# hamp2.net
KiCad netlist of a schematic drawn in EAGLE
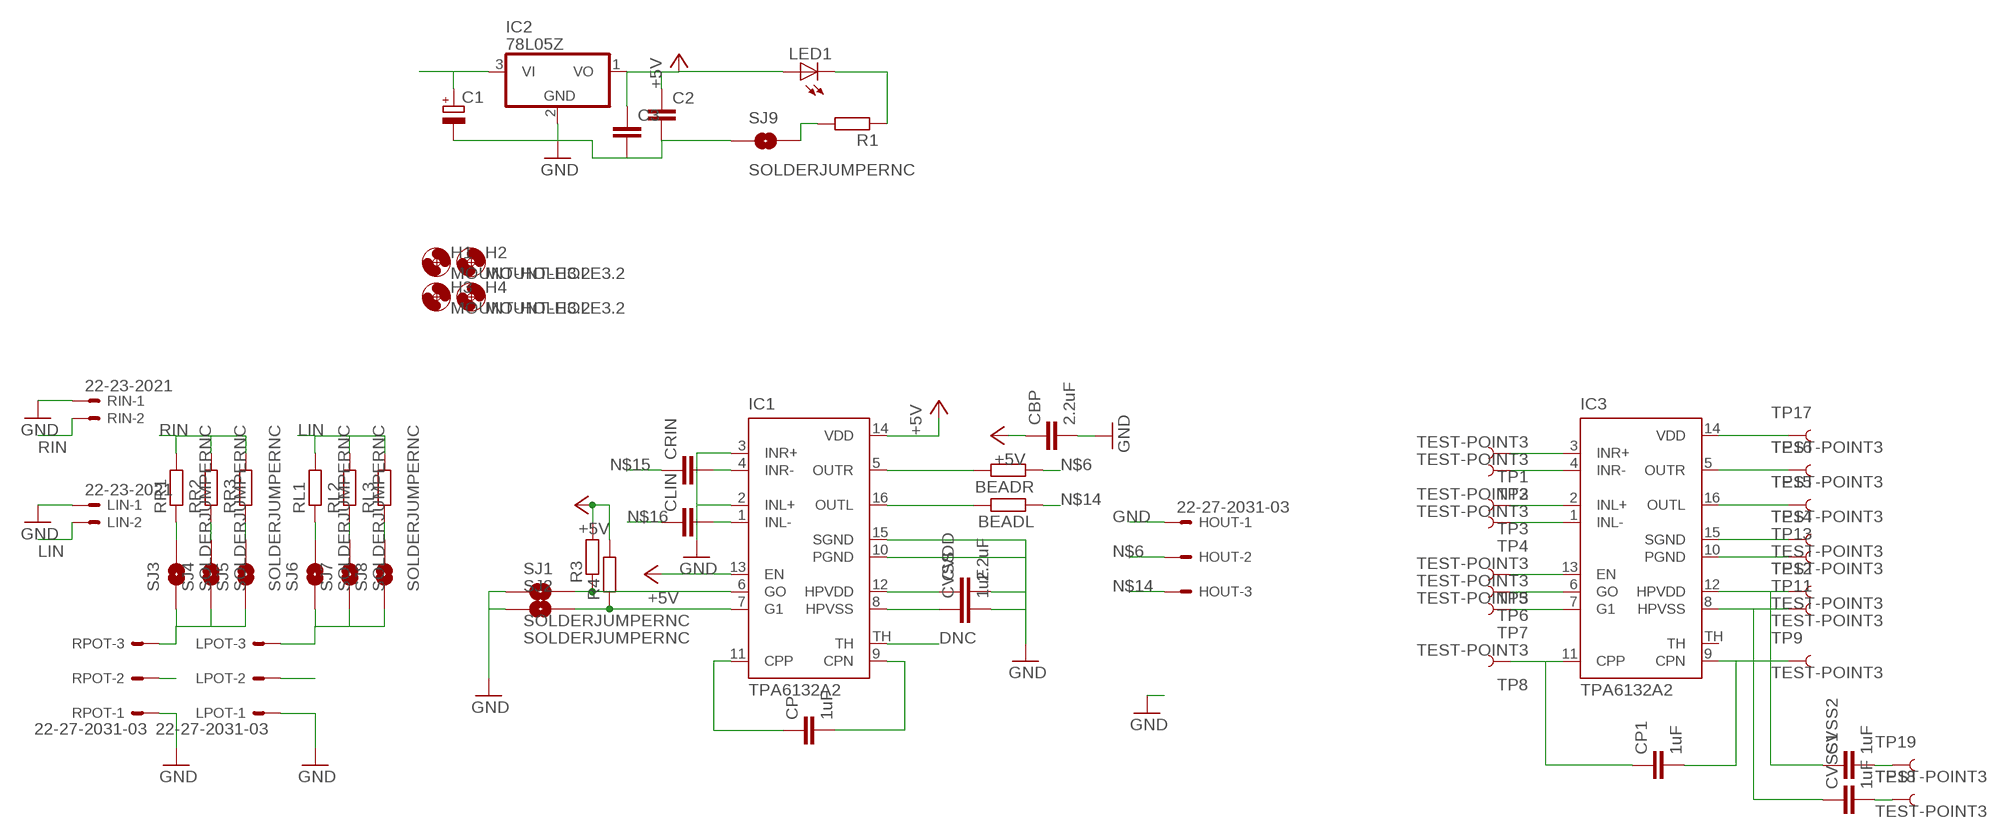
[diagram p0: schematic, sheet 1]

(export (version "E")
  (design (tool "Eeschema 10.0.6"))
  (components
    (comp (ref "BEADL")
      (value "R-EU_R0805")
      (footprint "eagle-import:R0805")
      (libsource (lib "eagle-import") (part "R-EU_R0805"))
    )
    (comp (ref "BEADR")
      (value "R-EU_R0805")
      (footprint "eagle-import:R0805")
      (libsource (lib "eagle-import") (part "R-EU_R0805"))
    )
    (comp (ref "C1")
      (value "CPOL-EUF")
      (footprint "eagle-import:PANASONIC_F")
      (libsource (lib "eagle-import") (part "CPOL-EUF"))
    )
    (comp (ref "C2")
      (value "C-EUC1210")
      (footprint "eagle-import:C1210")
      (libsource (lib "eagle-import") (part "resistor_C-EUC1210"))
    )
    (comp (ref "C3")
      (value "C-EUC0805")
      (footprint "eagle-import:C0805")
      (libsource (lib "eagle-import") (part "resistor_C-EUC0805"))
    )
    (comp (ref "CBP")
      (value "2.2uF")
      (footprint "eagle-import:C0805")
      (libsource (lib "eagle-import") (part "resistor_C-EUC0805"))
    )
    (comp (ref "CLIN")
      (value "C-EU050-055X075")
      (footprint "eagle-import:C050-055X075")
      (libsource (lib "eagle-import") (part "C-EU050-055X075"))
    )
    (comp (ref "CP")
      (value "1uF")
      (footprint "eagle-import:C0805")
      (libsource (lib "eagle-import") (part "resistor_C-EUC0805"))
    )
    (comp (ref "CP1")
      (value "1uF")
      (footprint "eagle-import:C0805")
      (libsource (lib "eagle-import") (part "resistor_C-EUC0805"))
    )
    (comp (ref "CRIN")
      (value "C-EU050-055X075")
      (footprint "eagle-import:C050-055X075")
      (libsource (lib "eagle-import") (part "C-EU050-055X075"))
    )
    (comp (ref "CVDD")
      (value "2.2uF")
      (footprint "eagle-import:C0805")
      (libsource (lib "eagle-import") (part "resistor_C-EUC0805"))
    )
    (comp (ref "CVSS")
      (value "1uF")
      (footprint "eagle-import:C0805")
      (libsource (lib "eagle-import") (part "resistor_C-EUC0805"))
    )
    (comp (ref "CVSS1")
      (value "1uF")
      (footprint "eagle-import:C0805")
      (libsource (lib "eagle-import") (part "resistor_C-EUC0805"))
    )
    (comp (ref "CVSS2")
      (value "1uF")
      (footprint "eagle-import:C0805")
      (libsource (lib "eagle-import") (part "resistor_C-EUC0805"))
    )
    (comp (ref "H1")
      (value "MOUNT-HOLE3.2")
      (footprint "eagle-import:3,2")
      (libsource (lib "eagle-import") (part "MOUNT-HOLE3.2"))
    )
    (comp (ref "H2")
      (value "MOUNT-HOLE3.2")
      (footprint "eagle-import:3,2")
      (libsource (lib "eagle-import") (part "MOUNT-HOLE3.2"))
    )
    (comp (ref "H3")
      (value "MOUNT-HOLE3.2")
      (footprint "eagle-import:3,2")
      (libsource (lib "eagle-import") (part "MOUNT-HOLE3.2"))
    )
    (comp (ref "H4")
      (value "MOUNT-HOLE3.2")
      (footprint "eagle-import:3,2")
      (libsource (lib "eagle-import") (part "MOUNT-HOLE3.2"))
    )
    (comp (ref "HOUT")
      (value "22-27-2031-03")
      (footprint "eagle-import:6410-03")
      (fields (field (name "OC_FARNELL") "unknown") (field (name "OC_NEWARK") "unknown"))
      (libsource (lib "eagle-import") (part "22-?-0327-2031"))
    )
    (comp (ref "IC1")
      (value "TPA6132A2")
      (footprint "eagle-import:QFN16")
      (fields (field (name "MPN") "TPA6132A2RTET"))
      (libsource (lib "eagle-import") (part "TPA6132A2"))
    )
    (comp (ref "IC2")
      (value "78L05Z")
      (footprint "eagle-import:TO92")
      (libsource (lib "eagle-import") (part "78ZL05"))
    )
    (comp (ref "IC3")
      (value "TPA6132A2")
      (footprint "eagle-import:QFN16")
      (fields
        (field (name "MPN") "TPA6132A2RTET")
        (field (name "MPN_1") "TPA6132A2RTET")
        (field (name "OC_FARNELL") "1697167")
        (field (name "OC_NEWARK") "46P3781")
      )
      (libsource (lib "eagle-import") (part "TPA6132A2"))
    )
    (comp (ref "LED1")
      (value "LEDCHIP-LED0805")
      (footprint "eagle-import:CHIP-LED0805")
      (libsource (lib "eagle-import") (part "LEDCHIP-LED0805"))
    )
    (comp (ref "LIN")
      (value "22-23-2021")
      (footprint "eagle-import:22-23-2021")
      (fields (field (name "MF") "MOLEX"))
      (libsource (lib "eagle-import") (part "22-23-2021"))
    )
    (comp (ref "LPOT")
      (value "22-27-2031-03")
      (footprint "eagle-import:6410-03")
      (fields (field (name "OC_FARNELL") "unknown") (field (name "OC_NEWARK") "unknown"))
      (libsource (lib "eagle-import") (part "22-?-0327-2031"))
    )
    (comp (ref "R1")
      (value "R-EU_R0805")
      (footprint "eagle-import:R0805")
      (libsource (lib "eagle-import") (part "R-EU_R0805"))
    )
    (comp (ref "R3")
      (value "R-EU_R0805")
      (footprint "eagle-import:R0805")
      (libsource (lib "eagle-import") (part "R-EU_R0805"))
    )
    (comp (ref "R4")
      (value "R-EU_R0805")
      (footprint "eagle-import:R0805")
      (libsource (lib "eagle-import") (part "R-EU_R0805"))
    )
    (comp (ref "RIN")
      (value "22-23-2021")
      (footprint "eagle-import:22-23-2021")
      (fields (field (name "MF") "MOLEX"))
      (libsource (lib "eagle-import") (part "22-23-2021"))
    )
    (comp (ref "RL1")
      (value "R-EU_R0805")
      (footprint "eagle-import:R0805")
      (libsource (lib "eagle-import") (part "R-EU_R0805"))
    )
    (comp (ref "RL2")
      (value "R-EU_R0805")
      (footprint "eagle-import:R0805")
      (libsource (lib "eagle-import") (part "R-EU_R0805"))
    )
    (comp (ref "RL3")
      (value "R-EU_R0805")
      (footprint "eagle-import:R0805")
      (libsource (lib "eagle-import") (part "R-EU_R0805"))
    )
    (comp (ref "RPOT")
      (value "22-27-2031-03")
      (footprint "eagle-import:6410-03")
      (fields (field (name "OC_FARNELL") "unknown") (field (name "OC_NEWARK") "unknown"))
      (libsource (lib "eagle-import") (part "22-?-0327-2031"))
    )
    (comp (ref "RR1")
      (value "R-EU_R0805")
      (footprint "eagle-import:R0805")
      (libsource (lib "eagle-import") (part "R-EU_R0805"))
    )
    (comp (ref "RR2")
      (value "R-EU_R0805")
      (footprint "eagle-import:R0805")
      (libsource (lib "eagle-import") (part "R-EU_R0805"))
    )
    (comp (ref "RR3")
      (value "R-EU_R0805")
      (footprint "eagle-import:R0805")
      (libsource (lib "eagle-import") (part "R-EU_R0805"))
    )
    (comp (ref "SJ1")
      (value "SOLDERJUMPERNC")
      (footprint "eagle-import:SJ_2S")
      (libsource (lib "eagle-import") (part "SOLDERJUMPERNC"))
    )
    (comp (ref "SJ2")
      (value "SOLDERJUMPERNC")
      (footprint "eagle-import:SJ_2S")
      (libsource (lib "eagle-import") (part "SOLDERJUMPERNC"))
    )
    (comp (ref "SJ3")
      (value "SOLDERJUMPERNC")
      (footprint "eagle-import:SJ_2S")
      (libsource (lib "eagle-import") (part "SOLDERJUMPERNC"))
    )
    (comp (ref "SJ4")
      (value "SOLDERJUMPERNC")
      (footprint "eagle-import:SJ_2S")
      (libsource (lib "eagle-import") (part "SOLDERJUMPERNC"))
    )
    (comp (ref "SJ5")
      (value "SOLDERJUMPERNC")
      (footprint "eagle-import:SJ_2S")
      (libsource (lib "eagle-import") (part "SOLDERJUMPERNC"))
    )
    (comp (ref "SJ6")
      (value "SOLDERJUMPERNC")
      (footprint "eagle-import:SJ_2S")
      (libsource (lib "eagle-import") (part "SOLDERJUMPERNC"))
    )
    (comp (ref "SJ7")
      (value "SOLDERJUMPERNC")
      (footprint "eagle-import:SJ_2S")
      (libsource (lib "eagle-import") (part "SOLDERJUMPERNC"))
    )
    (comp (ref "SJ8")
      (value "SOLDERJUMPERNC")
      (footprint "eagle-import:SJ_2S")
      (libsource (lib "eagle-import") (part "SOLDERJUMPERNC"))
    )
    (comp (ref "SJ9")
      (value "SOLDERJUMPERNC")
      (footprint "eagle-import:SJ_2S")
      (libsource (lib "eagle-import") (part "SOLDERJUMPERNC"))
    )
    (comp (ref "TP1")
      (value "TEST-POINT3")
      (footprint "eagle-import:PAD.03X.03")
      (libsource (lib "eagle-import") (part "TEST-POINT3"))
    )
    (comp (ref "TP2")
      (value "TEST-POINT3")
      (footprint "eagle-import:PAD.03X.03")
      (libsource (lib "eagle-import") (part "TEST-POINT3"))
    )
    (comp (ref "TP3")
      (value "TEST-POINT3")
      (footprint "eagle-import:PAD.03X.03")
      (libsource (lib "eagle-import") (part "TEST-POINT3"))
    )
    (comp (ref "TP4")
      (value "TEST-POINT3")
      (footprint "eagle-import:PAD.03X.03")
      (libsource (lib "eagle-import") (part "TEST-POINT3"))
    )
    (comp (ref "TP5")
      (value "TEST-POINT3")
      (footprint "eagle-import:PAD.03X.03")
      (libsource (lib "eagle-import") (part "TEST-POINT3"))
    )
    (comp (ref "TP6")
      (value "TEST-POINT3")
      (footprint "eagle-import:PAD.03X.03")
      (libsource (lib "eagle-import") (part "TEST-POINT3"))
    )
    (comp (ref "TP7")
      (value "TEST-POINT3")
      (footprint "eagle-import:PAD.03X.03")
      (libsource (lib "eagle-import") (part "TEST-POINT3"))
    )
    (comp (ref "TP8")
      (value "TEST-POINT3")
      (footprint "eagle-import:PAD.03X.03")
      (libsource (lib "eagle-import") (part "TEST-POINT3"))
    )
    (comp (ref "TP9")
      (value "TEST-POINT3")
      (footprint "eagle-import:PAD.03X.03")
      (libsource (lib "eagle-import") (part "TEST-POINT3"))
    )
    (comp (ref "TP11")
      (value "TEST-POINT3")
      (footprint "eagle-import:PAD.03X.03")
      (libsource (lib "eagle-import") (part "TEST-POINT3"))
    )
    (comp (ref "TP12")
      (value "TEST-POINT3")
      (footprint "eagle-import:PAD.03X.03")
      (libsource (lib "eagle-import") (part "TEST-POINT3"))
    )
    (comp (ref "TP13")
      (value "TEST-POINT3")
      (footprint "eagle-import:PAD.03X.03")
      (libsource (lib "eagle-import") (part "TEST-POINT3"))
    )
    (comp (ref "TP14")
      (value "TEST-POINT3")
      (footprint "eagle-import:PAD.03X.03")
      (libsource (lib "eagle-import") (part "TEST-POINT3"))
    )
    (comp (ref "TP15")
      (value "TEST-POINT3")
      (footprint "eagle-import:PAD.03X.03")
      (libsource (lib "eagle-import") (part "TEST-POINT3"))
    )
    (comp (ref "TP16")
      (value "TEST-POINT3")
      (footprint "eagle-import:PAD.03X.03")
      (libsource (lib "eagle-import") (part "TEST-POINT3"))
    )
    (comp (ref "TP17")
      (value "TEST-POINT3")
      (footprint "eagle-import:PAD.03X.03")
      (libsource (lib "eagle-import") (part "TEST-POINT3"))
    )
    (comp (ref "TP18")
      (value "TEST-POINT3")
      (footprint "eagle-import:PAD.03X.03")
      (libsource (lib "eagle-import") (part "TEST-POINT3"))
    )
    (comp (ref "TP19")
      (value "TEST-POINT3")
      (footprint "eagle-import:PAD.03X.03")
      (libsource (lib "eagle-import") (part "TEST-POINT3"))
    )
  )
  (nets
    (net (code "1") (name "+5V") (class "Default")
      (node (ref "C2") (pin "1") (pinfunction "1_1") (pintype "passive"))
      (node (ref "C3") (pin "1") (pinfunction "1_1") (pintype "passive"))
      (node (ref "CBP") (pin "1") (pinfunction "1_1") (pintype "passive"))
      (node (ref "IC1") (pin "13") (pinfunction "EN_13") (pintype "input"))
      (node (ref "IC1") (pin "14") (pinfunction "VDD_14") (pintype "power_in"))
      (node (ref "IC2") (pin "1") (pinfunction "VO_1") (pintype "passive"))
      (node (ref "LED1") (pin "A") (pinfunction "A_A") (pintype "passive"))
      (node (ref "R3") (pin "2") (pinfunction "2_2") (pintype "passive"))
      (node (ref "R4") (pin "2") (pinfunction "2_2") (pintype "passive"))
    )
    (net (code "2") (name "/DNC") (class "Default")
      (node (ref "IC1") (pin "TH") (pinfunction "TH_TH") (pintype "passive"))
    )
    (net (code "3") (name "/LIN") (class "Default")
      (node (ref "LIN") (pin "2") (pinfunction "S_2") (pintype "passive"))
      (node (ref "RL1") (pin "2") (pinfunction "2_2") (pintype "passive"))
      (node (ref "RL2") (pin "2") (pinfunction "2_2") (pintype "passive"))
      (node (ref "RL3") (pin "2") (pinfunction "2_2") (pintype "passive"))
    )
    (net (code "4") (name "/N$6") (class "Default")
      (node (ref "BEADR") (pin "1") (pinfunction "1_1") (pintype "passive"))
      (node (ref "HOUT") (pin "2") (pinfunction "S_2") (pintype "passive"))
    )
    (net (code "5") (name "/N$14") (class "Default")
      (node (ref "BEADL") (pin "1") (pinfunction "1_1") (pintype "passive"))
      (node (ref "HOUT") (pin "3") (pinfunction "S_3") (pintype "passive"))
    )
    (net (code "6") (name "/N$15") (class "Default")
      (node (ref "CRIN") (pin "1") (pinfunction "1_1") (pintype "passive"))
      (node (ref "RPOT") (pin "2") (pinfunction "S_2") (pintype "passive"))
      (node (ref "RR3") (pin "1") (pinfunction "1_1") (pintype "passive"))
      (node (ref "SJ5") (pin "2") (pinfunction "2_2") (pintype "passive"))
    )
    (net (code "7") (name "/N$16") (class "Default")
      (node (ref "CLIN") (pin "1") (pinfunction "1_1") (pintype "passive"))
      (node (ref "LPOT") (pin "2") (pinfunction "S_2") (pintype "passive"))
      (node (ref "RL3") (pin "1") (pinfunction "1_1") (pintype "passive"))
      (node (ref "SJ8") (pin "2") (pinfunction "2_2") (pintype "passive"))
    )
    (net (code "8") (name "/RIN") (class "Default")
      (node (ref "RIN") (pin "2") (pinfunction "S_2") (pintype "passive"))
      (node (ref "RR1") (pin "2") (pinfunction "2_2") (pintype "passive"))
      (node (ref "RR2") (pin "2") (pinfunction "2_2") (pintype "passive"))
      (node (ref "RR3") (pin "2") (pinfunction "2_2") (pintype "passive"))
    )
    (net (code "9") (name "GND") (class "Default")
      (node (ref "C1") (pin "-") (pinfunction "-_-") (pintype "passive"))
      (node (ref "C2") (pin "2") (pinfunction "2_2") (pintype "passive"))
      (node (ref "C3") (pin "2") (pinfunction "2_2") (pintype "passive"))
      (node (ref "CBP") (pin "2") (pinfunction "2_2") (pintype "passive"))
      (node (ref "CVDD") (pin "2") (pinfunction "2_2") (pintype "passive"))
      (node (ref "CVSS") (pin "2") (pinfunction "2_2") (pintype "passive"))
      (node (ref "HOUT") (pin "1") (pinfunction "S_1") (pintype "passive"))
      (node (ref "IC1") (pin "10") (pinfunction "PGND_10") (pintype "power_in"))
      (node (ref "IC1") (pin "15") (pinfunction "SGND_15") (pintype "power_in"))
      (node (ref "IC1") (pin "2") (pinfunction "INL+_2") (pintype "input"))
      (node (ref "IC1") (pin "3") (pinfunction "INR+_3") (pintype "input"))
      (node (ref "IC2") (pin "2") (pinfunction "GND_2") (pintype "passive"))
      (node (ref "LIN") (pin "1") (pinfunction "S_1") (pintype "passive"))
      (node (ref "LPOT") (pin "1") (pinfunction "S_1") (pintype "passive"))
      (node (ref "RIN") (pin "1") (pinfunction "S_1") (pintype "passive"))
      (node (ref "RPOT") (pin "1") (pinfunction "S_1") (pintype "passive"))
      (node (ref "SJ1") (pin "1") (pinfunction "1_1") (pintype "passive"))
      (node (ref "SJ2") (pin "1") (pinfunction "1_1") (pintype "passive"))
      (node (ref "SJ9") (pin "1") (pinfunction "1_1") (pintype "passive"))
    )
    (net (code "10") (name "Net-(IC1-CPN)") (class "Default")
      (node (ref "CP") (pin "2") (pinfunction "2_2") (pintype "passive"))
      (node (ref "IC1") (pin "9") (pinfunction "CPN_9") (pintype "passive"))
    )
    (net (code "11") (name "Net-(IC1-CPP)") (class "Default")
      (node (ref "CP") (pin "1") (pinfunction "1_1") (pintype "passive"))
      (node (ref "IC1") (pin "11") (pinfunction "CPP_11") (pintype "passive"))
    )
    (net (code "12") (name "Net-(IC1-G1)") (class "Default")
      (node (ref "IC1") (pin "7") (pinfunction "G1_7") (pintype "input"))
      (node (ref "R4") (pin "1") (pinfunction "1_1") (pintype "passive"))
      (node (ref "SJ2") (pin "2") (pinfunction "2_2") (pintype "passive"))
    )
    (net (code "13") (name "Net-(IC1-GO)") (class "Default")
      (node (ref "IC1") (pin "6") (pinfunction "GO_6") (pintype "input"))
      (node (ref "R3") (pin "1") (pinfunction "1_1") (pintype "passive"))
      (node (ref "SJ1") (pin "2") (pinfunction "2_2") (pintype "passive"))
    )
    (net (code "14") (name "Net-(IC1-HPVDD)") (class "Default")
      (node (ref "CVDD") (pin "1") (pinfunction "1_1") (pintype "passive"))
      (node (ref "IC1") (pin "12") (pinfunction "HPVDD_12") (pintype "passive"))
    )
    (net (code "15") (name "Net-(IC1-HPVSS)") (class "Default")
      (node (ref "CVSS") (pin "1") (pinfunction "1_1") (pintype "passive"))
      (node (ref "IC1") (pin "8") (pinfunction "HPVSS_8") (pintype "passive"))
    )
    (net (code "16") (name "Net-(IC1-INL-)") (class "Default")
      (node (ref "CLIN") (pin "2") (pinfunction "2_2") (pintype "passive"))
      (node (ref "IC1") (pin "1") (pinfunction "INL-_1") (pintype "input"))
    )
    (net (code "17") (name "Net-(IC1-INR-)") (class "Default")
      (node (ref "CRIN") (pin "2") (pinfunction "2_2") (pintype "passive"))
      (node (ref "IC1") (pin "4") (pinfunction "INR-_4") (pintype "input"))
    )
    (net (code "18") (name "Net-(IC1-OUTL)") (class "Default")
      (node (ref "BEADL") (pin "2") (pinfunction "2_2") (pintype "passive"))
      (node (ref "IC1") (pin "16") (pinfunction "OUTL_16") (pintype "output"))
    )
    (net (code "19") (name "Net-(IC1-OUTR)") (class "Default")
      (node (ref "BEADR") (pin "2") (pinfunction "2_2") (pintype "passive"))
      (node (ref "IC1") (pin "5") (pinfunction "OUTR_5") (pintype "output"))
    )
    (net (code "20") (name "Net-(IC2-VI)") (class "Default")
      (node (ref "C1") (pin "+") (pinfunction "+_+") (pintype "passive"))
      (node (ref "IC2") (pin "3") (pinfunction "VI_3") (pintype "input"))
    )
    (net (code "21") (name "Net-(IC3-CPN)") (class "Default")
      (node (ref "CP1") (pin "2") (pinfunction "2_2") (pintype "passive"))
      (node (ref "IC3") (pin "9") (pinfunction "CPN_9") (pintype "passive"))
      (node (ref "TP9") (pin "P$1") (pinfunction "1_P$1") (pintype "bidirectional"))
    )
    (net (code "22") (name "Net-(IC3-CPP)") (class "Default")
      (node (ref "CP1") (pin "1") (pinfunction "1_1") (pintype "passive"))
      (node (ref "IC3") (pin "11") (pinfunction "CPP_11") (pintype "passive"))
      (node (ref "TP8") (pin "P$1") (pinfunction "1_P$1") (pintype "bidirectional"))
    )
    (net (code "23") (name "Net-(IC3-EN)") (class "Default")
      (node (ref "IC3") (pin "13") (pinfunction "EN_13") (pintype "input"))
      (node (ref "TP5") (pin "P$1") (pinfunction "1_P$1") (pintype "bidirectional"))
    )
    (net (code "24") (name "Net-(IC3-G1)") (class "Default")
      (node (ref "IC3") (pin "7") (pinfunction "G1_7") (pintype "input"))
      (node (ref "TP7") (pin "P$1") (pinfunction "1_P$1") (pintype "bidirectional"))
    )
    (net (code "25") (name "Net-(IC3-GO)") (class "Default")
      (node (ref "IC3") (pin "6") (pinfunction "GO_6") (pintype "input"))
      (node (ref "TP6") (pin "P$1") (pinfunction "1_P$1") (pintype "bidirectional"))
    )
    (net (code "26") (name "Net-(IC3-HPVDD)") (class "Default")
      (node (ref "CVSS2") (pin "1") (pinfunction "1_1") (pintype "passive"))
      (node (ref "IC3") (pin "12") (pinfunction "HPVDD_12") (pintype "passive"))
      (node (ref "TP12") (pin "P$1") (pinfunction "1_P$1") (pintype "bidirectional"))
    )
    (net (code "27") (name "Net-(IC3-HPVSS)") (class "Default")
      (node (ref "CVSS1") (pin "1") (pinfunction "1_1") (pintype "passive"))
      (node (ref "IC3") (pin "8") (pinfunction "HPVSS_8") (pintype "passive"))
      (node (ref "TP11") (pin "P$1") (pinfunction "1_P$1") (pintype "bidirectional"))
    )
    (net (code "28") (name "Net-(IC3-INL+)") (class "Default")
      (node (ref "IC3") (pin "2") (pinfunction "INL+_2") (pintype "input"))
      (node (ref "TP3") (pin "P$1") (pinfunction "1_P$1") (pintype "bidirectional"))
    )
    (net (code "29") (name "Net-(IC3-INL-)") (class "Default")
      (node (ref "IC3") (pin "1") (pinfunction "INL-_1") (pintype "input"))
      (node (ref "TP4") (pin "P$1") (pinfunction "1_P$1") (pintype "bidirectional"))
    )
    (net (code "30") (name "Net-(IC3-INR+)") (class "Default")
      (node (ref "IC3") (pin "3") (pinfunction "INR+_3") (pintype "input"))
      (node (ref "TP1") (pin "P$1") (pinfunction "1_P$1") (pintype "bidirectional"))
    )
    (net (code "31") (name "Net-(IC3-INR-)") (class "Default")
      (node (ref "IC3") (pin "4") (pinfunction "INR-_4") (pintype "input"))
      (node (ref "TP2") (pin "P$1") (pinfunction "1_P$1") (pintype "bidirectional"))
    )
    (net (code "32") (name "Net-(IC3-OUTL)") (class "Default")
      (node (ref "IC3") (pin "16") (pinfunction "OUTL_16") (pintype "output"))
      (node (ref "TP15") (pin "P$1") (pinfunction "1_P$1") (pintype "bidirectional"))
    )
    (net (code "33") (name "Net-(IC3-OUTR)") (class "Default")
      (node (ref "IC3") (pin "5") (pinfunction "OUTR_5") (pintype "output"))
      (node (ref "TP16") (pin "P$1") (pinfunction "1_P$1") (pintype "bidirectional"))
    )
    (net (code "34") (name "Net-(IC3-PGND)") (class "Default")
      (node (ref "IC3") (pin "10") (pinfunction "PGND_10") (pintype "power_in"))
      (node (ref "TP13") (pin "P$1") (pinfunction "1_P$1") (pintype "bidirectional"))
    )
    (net (code "35") (name "Net-(IC3-SGND)") (class "Default")
      (node (ref "IC3") (pin "15") (pinfunction "SGND_15") (pintype "power_in"))
      (node (ref "TP14") (pin "P$1") (pinfunction "1_P$1") (pintype "bidirectional"))
    )
    (net (code "36") (name "Net-(IC3-VDD)") (class "Default")
      (node (ref "IC3") (pin "14") (pinfunction "VDD_14") (pintype "power_in"))
      (node (ref "TP17") (pin "P$1") (pinfunction "1_P$1") (pintype "bidirectional"))
    )
    (net (code "37") (name "Net-(LED1-PadC)") (class "Default")
      (node (ref "LED1") (pin "C") (pinfunction "C_C") (pintype "passive"))
      (node (ref "R1") (pin "1") (pinfunction "1_1") (pintype "passive"))
    )
    (net (code "38") (name "Net-(LPOTC-S)") (class "Default")
      (node (ref "LPOT") (pin "3") (pinfunction "S_3") (pintype "passive"))
      (node (ref "SJ6") (pin "1") (pinfunction "1_1") (pintype "passive"))
      (node (ref "SJ7") (pin "1") (pinfunction "1_1") (pintype "passive"))
      (node (ref "SJ8") (pin "1") (pinfunction "1_1") (pintype "passive"))
    )
    (net (code "39") (name "Net-(R1-Pad2)") (class "Default")
      (node (ref "R1") (pin "2") (pinfunction "2_2") (pintype "passive"))
      (node (ref "SJ9") (pin "2") (pinfunction "2_2") (pintype "passive"))
    )
    (net (code "40") (name "Net-(RL1-Pad1)") (class "Default")
      (node (ref "RL1") (pin "1") (pinfunction "1_1") (pintype "passive"))
      (node (ref "SJ6") (pin "2") (pinfunction "2_2") (pintype "passive"))
    )
    (net (code "41") (name "Net-(RL2-Pad1)") (class "Default")
      (node (ref "RL2") (pin "1") (pinfunction "1_1") (pintype "passive"))
      (node (ref "SJ7") (pin "2") (pinfunction "2_2") (pintype "passive"))
    )
    (net (code "42") (name "Net-(RPOTC-S)") (class "Default")
      (node (ref "RPOT") (pin "3") (pinfunction "S_3") (pintype "passive"))
      (node (ref "SJ3") (pin "1") (pinfunction "1_1") (pintype "passive"))
      (node (ref "SJ4") (pin "1") (pinfunction "1_1") (pintype "passive"))
      (node (ref "SJ5") (pin "1") (pinfunction "1_1") (pintype "passive"))
    )
    (net (code "43") (name "Net-(RR1-Pad1)") (class "Default")
      (node (ref "RR1") (pin "1") (pinfunction "1_1") (pintype "passive"))
      (node (ref "SJ3") (pin "2") (pinfunction "2_2") (pintype "passive"))
    )
    (net (code "44") (name "Net-(RR2-Pad1)") (class "Default")
      (node (ref "RR2") (pin "1") (pinfunction "1_1") (pintype "passive"))
      (node (ref "SJ4") (pin "2") (pinfunction "2_2") (pintype "passive"))
    )
    (net (code "45") (name "Net-(TP18-1)") (class "Default")
      (node (ref "CVSS1") (pin "2") (pinfunction "2_2") (pintype "passive"))
      (node (ref "TP18") (pin "P$1") (pinfunction "1_P$1") (pintype "bidirectional"))
    )
    (net (code "46") (name "Net-(TP19-1)") (class "Default")
      (node (ref "CVSS2") (pin "2") (pinfunction "2_2") (pintype "passive"))
      (node (ref "TP19") (pin "P$1") (pinfunction "1_P$1") (pintype "bidirectional"))
    )
    (net (code "47") (name "unconnected-(IC3-PadTH)") (class "Default")
      (node (ref "IC3") (pin "TH") (pinfunction "TH_TH") (pintype "passive"))
    )
  )
)
